# log_storage.net
KiCad netlist of a schematic drawn in Altium Designer
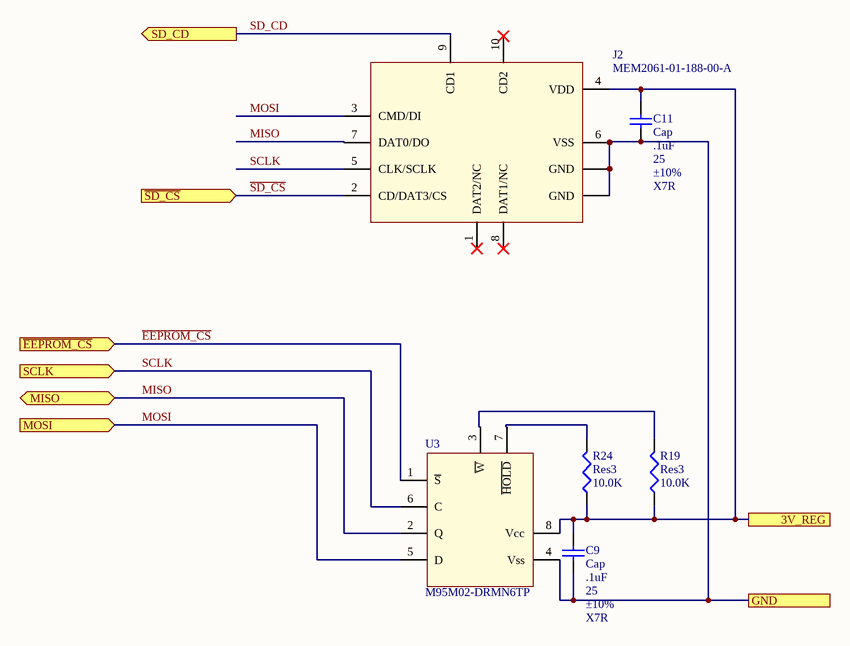
[diagram p0: log_storage.SchDoc]

(export (version "E")
  (design (tool "Eeschema 10.0.6"))
  (components
    (comp (ref "C9")
      (value "Cap")
      (footprint "CAPC2012X09M")
      (description "CAP CER .1uF 25v X7R 0805")
      (fields
        (field (name "ALTIUM_VALUE") ".1uF")
        (field (name "WV") "25")
        (field (name "TOLERANCE") "±10%")
        (field (name "TYPE") "X7R")
        (field (name "MPN") "C0805C104K3RACTU")
      )
      (libsource (lib "esd_library") (part "CAP-X7R-.1uF-25V-±10%"))
    )
    (comp (ref "C11")
      (value "Cap")
      (footprint "CAPC2012X09M")
      (description "CAP CER .1uF 25v X7R 0805")
      (fields
        (field (name "ALTIUM_VALUE") ".1uF")
        (field (name "WV") "25")
        (field (name "TOLERANCE") "±10%")
        (field (name "TYPE") "X7R")
        (field (name "MPN") "C0805C104K3RACTU")
      )
      (libsource (lib "esd_library") (part "CAP-X7R-.1uF-25V-±10%"))
    )
    (comp (ref "J2")
      (value "MEM2061-01-188-00-A")
      (footprint "GCT_MEM2061-01-188-00-A_REVA")
      (description "10 _8 + 2_ Position Card Connector microSDâ„¢ Surface Mount, Right Angle Gold")
      (fields (field (name "MF") "Global Connector Technology"))
      (libsource (lib "MEM2061-01-188-00-A_REVA") (part "MEM2061-01-188-00-A_REVA"))
    )
    (comp (ref "R19")
      (value "Res3")
      (footprint "RESC2112X05M")
      (description "RES SMD 10.0K OHM 1% 1/8W 0805")
      (fields (field (name "ALTIUM_VALUE") "10.0K") (field (name "MPN") "CRCW080510K0FKEA"))
      (libsource (lib "esd_library") (part "Resistor_10.0K"))
    )
    (comp (ref "R24")
      (value "Res3")
      (footprint "RESC2112X05M")
      (description "RES SMD 10.0K OHM 1% 1/8W 0805")
      (fields (field (name "ALTIUM_VALUE") "10.0K") (field (name "MPN") "CRCW080510K0FKEA"))
      (libsource (lib "esd_library") (part "Resistor_10.0K"))
    )
    (comp (ref "U3")
      (value "M95M02-DRMN6TP")
      (footprint "SOIC8-1.27-5X4MM")
      (description "EEPROM Memory IC 2Mb _256K x 8_ SPI 5MHz 8-SO")
      (fields (field (name "MF") "STMicroelectronics"))
      (libsource (lib "MCU-M95M02-DRMN6TP_SOIC8_") (part "MCU-M95M02-DRMN6TP(SOIC8)"))
    )
  )
  (nets
    (net (code "1") (name "/3V_REG") (class "Default")
      (node (ref "C11") (pin "2") (pinfunction "2_2") (pintype "passive"))
      (node (ref "C9") (pin "2") (pinfunction "2_2") (pintype "passive"))
      (node (ref "J2") (pin "4") (pinfunction "VDD_4") (pintype "passive"))
      (node (ref "R19") (pin "1") (pinfunction "1_1") (pintype "passive"))
      (node (ref "R24") (pin "1") (pinfunction "1_1") (pintype "passive"))
      (node (ref "U3") (pin "8") (pinfunction "Vcc_8") (pintype "passive"))
    )
    (net (code "2") (name "/GND") (class "Default")
      (node (ref "C11") (pin "1") (pinfunction "1_1") (pintype "passive"))
      (node (ref "C9") (pin "1") (pinfunction "1_1") (pintype "passive"))
      (node (ref "J2") (pin "6") (pinfunction "VSS_6") (pintype "passive"))
      (node (ref "J2") (pin "GND") (pinfunction "GND_GND") (pintype "passive"))
      (node (ref "U3") (pin "4") (pinfunction "Vss_4") (pintype "passive"))
    )
    (net (code "3") (name "/MISO") (class "Default")
      (node (ref "J2") (pin "7") (pinfunction "DAT0/DO_7") (pintype "passive"))
      (node (ref "U3") (pin "2") (pinfunction "Q_2") (pintype "passive"))
    )
    (net (code "4") (name "/MOSI") (class "Default")
      (node (ref "J2") (pin "3") (pinfunction "CMD/DI_3") (pintype "passive"))
      (node (ref "U3") (pin "5") (pinfunction "D_5") (pintype "passive"))
    )
    (net (code "5") (name "/SCLK") (class "Default")
      (node (ref "J2") (pin "5") (pinfunction "CLK/SCLK_5") (pintype "passive"))
      (node (ref "U3") (pin "6") (pinfunction "C_6") (pintype "passive"))
    )
    (net (code "6") (name "/SD_CD") (class "Default")
      (node (ref "J2") (pin "9") (pinfunction "CD1_9") (pintype "passive"))
    )
    (net (code "7") (name "/~{EEPROM_CS}") (class "Default")
      (node (ref "U3") (pin "1") (pinfunction "~{S}_1") (pintype "passive"))
    )
    (net (code "8") (name "/~{SD_CS}") (class "Default")
      (node (ref "J2") (pin "2") (pinfunction "CD/DAT3/CS_2") (pintype "passive"))
    )
    (net (code "9") (name "Net-(U3-~{HOLD})") (class "Default")
      (node (ref "R24") (pin "2") (pinfunction "2_2") (pintype "passive"))
      (node (ref "U3") (pin "7") (pinfunction "~{HOLD}_7") (pintype "passive"))
    )
    (net (code "10") (name "Net-(U3-~{W})") (class "Default")
      (node (ref "R19") (pin "2") (pinfunction "2_2") (pintype "passive"))
      (node (ref "U3") (pin "3") (pinfunction "~{W}_3") (pintype "passive"))
    )
    (net (code "11") (name "unconnected-(J2-CD2-Pad10)") (class "Default")
      (node (ref "J2") (pin "10") (pinfunction "CD2_10") (pintype "passive+no_connect"))
    )
    (net (code "12") (name "unconnected-(J2-DAT1{slash}NC-Pad8)") (class "Default")
      (node (ref "J2") (pin "8") (pinfunction "DAT1/NC_8") (pintype "passive+no_connect"))
    )
    (net (code "13") (name "unconnected-(J2-DAT2{slash}NC-Pad1)") (class "Default")
      (node (ref "J2") (pin "1") (pinfunction "DAT2/NC_1") (pintype "passive+no_connect"))
    )
  )
)
